# pocz_tkowy_schemat.net
KiCad netlist of a schematic drawn in EAGLE
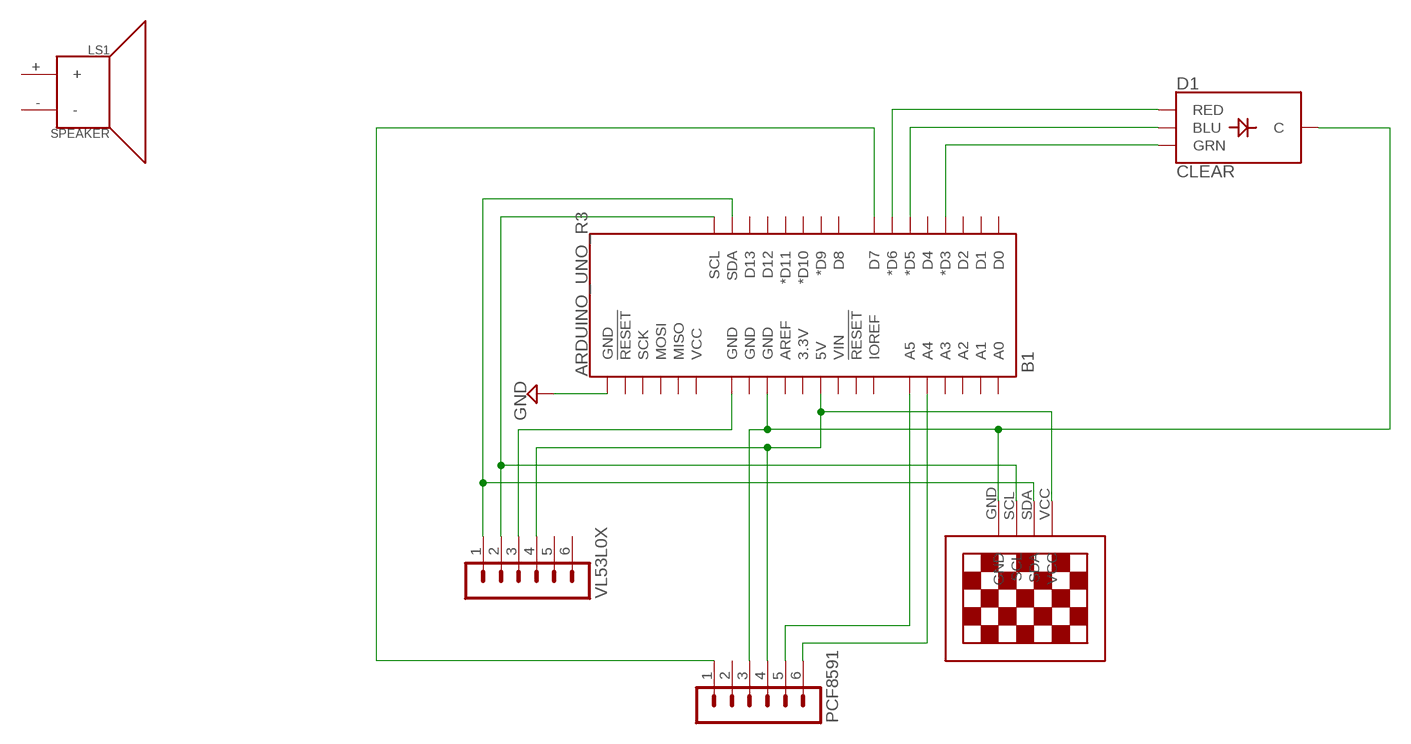
[diagram p0: schematic, sheet 1]

(export (version "E")
  (design (tool "Eeschema 10.0.6"))
  (components
    (comp (ref "B1")
      (value "ARDUINO_UNO_R3")
      (footprint "eagle-import:ARDUINO_R3")
      (libsource (lib "eagle-import") (part "ARDUINO_UNO_R3"))
    )
    (comp (ref "D1")
      (value "CLEAR")
      (footprint "eagle-import:LED-RGB-THRU")
      (libsource (lib "eagle-import") (part "LED-RGB-CCCLEAR"))
    )
    (comp (ref "LS1")
      (value "SPEAKER")
      (footprint "eagle-import:PCB_MOUNT_SPEAKER")
      (libsource (lib "eagle-import") (part "SPEAKER"))
    )
    (comp (ref "PCF8591")
      (value "MA06-1")
      (footprint "eagle-import:MA06-1")
      (libsource (lib "eagle-import") (part "MA06-1"))
    )
    (comp (ref "U$1")
      (value "13\"OLED13\"OLED")
      (footprint "eagle-import:1.3_OLED")
      (libsource (lib "eagle-import") (part "13{dblquote}OLED13{dblquote}OLED"))
    )
    (comp (ref "VL53L0X")
      (value "MA06-1")
      (footprint "eagle-import:MA06-1")
      (libsource (lib "eagle-import") (part "MA06-1"))
    )
  )
  (nets
    (net (code "1") (name "GND") (class "Default")
      (node (ref "B1") (pin "GND@1") (pinfunction "GND_GND@1") (pintype "bidirectional"))
    )
    (net (code "2") (name "Net-(B1-*D3)") (class "Default")
      (node (ref "B1") (pin "D3") (pinfunction "*D3_D3") (pintype "bidirectional"))
      (node (ref "D1") (pin "3") (pinfunction "GRN_3") (pintype "bidirectional"))
    )
    (net (code "3") (name "Net-(B1-*D5)") (class "Default")
      (node (ref "B1") (pin "D5") (pinfunction "*D5_D5") (pintype "bidirectional"))
      (node (ref "D1") (pin "4") (pinfunction "BLU_4") (pintype "bidirectional"))
    )
    (net (code "4") (name "Net-(B1-*D6)") (class "Default")
      (node (ref "B1") (pin "D6") (pinfunction "*D6_D6") (pintype "bidirectional"))
      (node (ref "D1") (pin "1") (pinfunction "RED_1") (pintype "bidirectional"))
    )
    (net (code "5") (name "Net-(B1-GND-PadGND@2)") (class "Default")
      (node (ref "B1") (pin "GND@2") (pinfunction "GND_GND@2") (pintype "bidirectional"))
      (node (ref "VL53L0X") (pin "3") (pinfunction "3_3") (pintype "passive"))
    )
    (net (code "6") (name "Net-(B1-Pad5V)") (class "Default")
      (node (ref "B1") (pin "5V") (pinfunction "5V_5V") (pintype "bidirectional"))
      (node (ref "PCF8591") (pin "4") (pinfunction "4_4") (pintype "passive"))
      (node (ref "U$1") (pin "VCC") (pinfunction "VCC_VCC") (pintype "bidirectional"))
      (node (ref "VL53L0X") (pin "4") (pinfunction "4_4") (pintype "passive"))
    )
    (net (code "7") (name "Net-(B1-PadA4)") (class "Default")
      (node (ref "B1") (pin "A4") (pinfunction "A4_A4") (pintype "bidirectional"))
      (node (ref "PCF8591") (pin "6") (pinfunction "6_6") (pintype "passive"))
    )
    (net (code "8") (name "Net-(B1-PadA5)") (class "Default")
      (node (ref "B1") (pin "A5") (pinfunction "A5_A5") (pintype "bidirectional"))
      (node (ref "PCF8591") (pin "5") (pinfunction "5_5") (pintype "passive"))
    )
    (net (code "9") (name "Net-(B1-PadD7)") (class "Default")
      (node (ref "B1") (pin "D7") (pinfunction "D7_D7") (pintype "bidirectional"))
      (node (ref "PCF8591") (pin "1") (pinfunction "1_1") (pintype "passive"))
    )
    (net (code "10") (name "Net-(B1-PadSCL)") (class "Default")
      (node (ref "B1") (pin "SCL") (pinfunction "SCL_SCL") (pintype "bidirectional"))
      (node (ref "U$1") (pin "SCL") (pinfunction "SCL_SCL") (pintype "bidirectional"))
      (node (ref "VL53L0X") (pin "2") (pinfunction "2_2") (pintype "passive"))
    )
    (net (code "11") (name "Net-(B1-PadSDA)") (class "Default")
      (node (ref "B1") (pin "SDA") (pinfunction "SDA_SDA") (pintype "bidirectional"))
      (node (ref "U$1") (pin "SDA") (pinfunction "SDA_SDA") (pintype "bidirectional"))
      (node (ref "VL53L0X") (pin "1") (pinfunction "1_1") (pintype "passive"))
    )
    (net (code "12") (name "Net-(D1-C)") (class "Default")
      (node (ref "B1") (pin "GND@4") (pinfunction "GND_GND@4") (pintype "bidirectional"))
      (node (ref "D1") (pin "2") (pinfunction "C_2") (pintype "bidirectional"))
      (node (ref "PCF8591") (pin "3") (pinfunction "3_3") (pintype "passive"))
      (node (ref "U$1") (pin "GND") (pinfunction "GND_GND") (pintype "bidirectional"))
    )
    (net (code "13") (name "unconnected-(B1-*D9-PadD9)") (class "Default")
      (node (ref "B1") (pin "D9") (pinfunction "*D9_D9") (pintype "bidirectional"))
    )
    (net (code "14") (name "unconnected-(B1-*D10-PadD10)") (class "Default")
      (node (ref "B1") (pin "D10") (pinfunction "*D10_D10") (pintype "bidirectional"))
    )
    (net (code "15") (name "unconnected-(B1-*D11-PadD11)") (class "Default")
      (node (ref "B1") (pin "D11") (pinfunction "*D11_D11") (pintype "bidirectional"))
    )
    (net (code "16") (name "unconnected-(B1-GND-PadGND@3)") (class "Default")
      (node (ref "B1") (pin "GND@3") (pinfunction "GND_GND@3") (pintype "bidirectional"))
    )
    (net (code "17") (name "unconnected-(B1-Pad3.3V)") (class "Default")
      (node (ref "B1") (pin "3.3V") (pinfunction "3.3V_3.3V") (pintype "bidirectional"))
    )
    (net (code "18") (name "unconnected-(B1-PadA0)") (class "Default")
      (node (ref "B1") (pin "A0") (pinfunction "A0_A0") (pintype "bidirectional"))
    )
    (net (code "19") (name "unconnected-(B1-PadA1)") (class "Default")
      (node (ref "B1") (pin "A1") (pinfunction "A1_A1") (pintype "bidirectional"))
    )
    (net (code "20") (name "unconnected-(B1-PadA2)") (class "Default")
      (node (ref "B1") (pin "A2") (pinfunction "A2_A2") (pintype "bidirectional"))
    )
    (net (code "21") (name "unconnected-(B1-PadA3)") (class "Default")
      (node (ref "B1") (pin "A3") (pinfunction "A3_A3") (pintype "bidirectional"))
    )
    (net (code "22") (name "unconnected-(B1-PadAREF)") (class "Default")
      (node (ref "B1") (pin "AREF") (pinfunction "AREF_AREF") (pintype "bidirectional"))
    )
    (net (code "23") (name "unconnected-(B1-PadD0)") (class "Default")
      (node (ref "B1") (pin "D0") (pinfunction "D0_D0") (pintype "bidirectional"))
    )
    (net (code "24") (name "unconnected-(B1-PadD1)") (class "Default")
      (node (ref "B1") (pin "D1") (pinfunction "D1_D1") (pintype "bidirectional"))
    )
    (net (code "25") (name "unconnected-(B1-PadD2)") (class "Default")
      (node (ref "B1") (pin "D2") (pinfunction "D2_D2") (pintype "bidirectional"))
    )
    (net (code "26") (name "unconnected-(B1-PadD4)") (class "Default")
      (node (ref "B1") (pin "D4") (pinfunction "D4_D4") (pintype "bidirectional"))
    )
    (net (code "27") (name "unconnected-(B1-PadD8)") (class "Default")
      (node (ref "B1") (pin "D8") (pinfunction "D8_D8") (pintype "bidirectional"))
    )
    (net (code "28") (name "unconnected-(B1-PadD12)") (class "Default")
      (node (ref "B1") (pin "D12") (pinfunction "D12_D12") (pintype "bidirectional"))
    )
    (net (code "29") (name "unconnected-(B1-PadD13)") (class "Default")
      (node (ref "B1") (pin "D13") (pinfunction "D13_D13") (pintype "bidirectional"))
    )
    (net (code "30") (name "unconnected-(B1-PadIOREF)") (class "Default")
      (node (ref "B1") (pin "IOREF") (pinfunction "IOREF_IOREF") (pintype "bidirectional"))
    )
    (net (code "31") (name "unconnected-(B1-PadMISO)") (class "Default")
      (node (ref "B1") (pin "MISO") (pinfunction "MISO_MISO") (pintype "bidirectional"))
    )
    (net (code "32") (name "unconnected-(B1-PadMOSI)") (class "Default")
      (node (ref "B1") (pin "MOSI") (pinfunction "MOSI_MOSI") (pintype "bidirectional"))
    )
    (net (code "33") (name "unconnected-(B1-PadSCK)") (class "Default")
      (node (ref "B1") (pin "SCK") (pinfunction "SCK_SCK") (pintype "bidirectional"))
    )
    (net (code "34") (name "unconnected-(B1-PadVCC)") (class "Default")
      (node (ref "B1") (pin "VCC") (pinfunction "VCC_VCC") (pintype "bidirectional"))
    )
    (net (code "35") (name "unconnected-(B1-PadVIN)") (class "Default")
      (node (ref "B1") (pin "VIN") (pinfunction "VIN_VIN") (pintype "bidirectional"))
    )
    (net (code "36") (name "unconnected-(B1-~{RESET}-PadRESET@1)") (class "Default")
      (node (ref "B1") (pin "RESET@1") (pinfunction "~{RESET}_RESET@1") (pintype "bidirectional"))
    )
    (net (code "37") (name "unconnected-(B1-~{RESET}-PadRESET@2)") (class "Default")
      (node (ref "B1") (pin "RESET@2") (pinfunction "~{RESET}_RESET@2") (pintype "bidirectional"))
    )
    (net (code "38") (name "unconnected-(LS1-Pad+)") (class "Default")
      (node (ref "LS1") (pin "+") (pinfunction "+_+") (pintype "bidirectional"))
    )
    (net (code "39") (name "unconnected-(LS1-Pad-)") (class "Default")
      (node (ref "LS1") (pin "-") (pinfunction "-_-") (pintype "bidirectional"))
    )
    (net (code "40") (name "unconnected-(PCF8591-Pad2)") (class "Default")
      (node (ref "PCF8591") (pin "2") (pinfunction "2_2") (pintype "passive"))
    )
    (net (code "41") (name "unconnected-(VL53L0X-Pad5)") (class "Default")
      (node (ref "VL53L0X") (pin "5") (pinfunction "5_5") (pintype "passive"))
    )
    (net (code "42") (name "unconnected-(VL53L0X-Pad6)") (class "Default")
      (node (ref "VL53L0X") (pin "6") (pinfunction "6_6") (pintype "passive"))
    )
  )
)
